# CUK_3Ph_sig_conditioner.net
KiCad netlist of a schematic drawn in Altium Designer
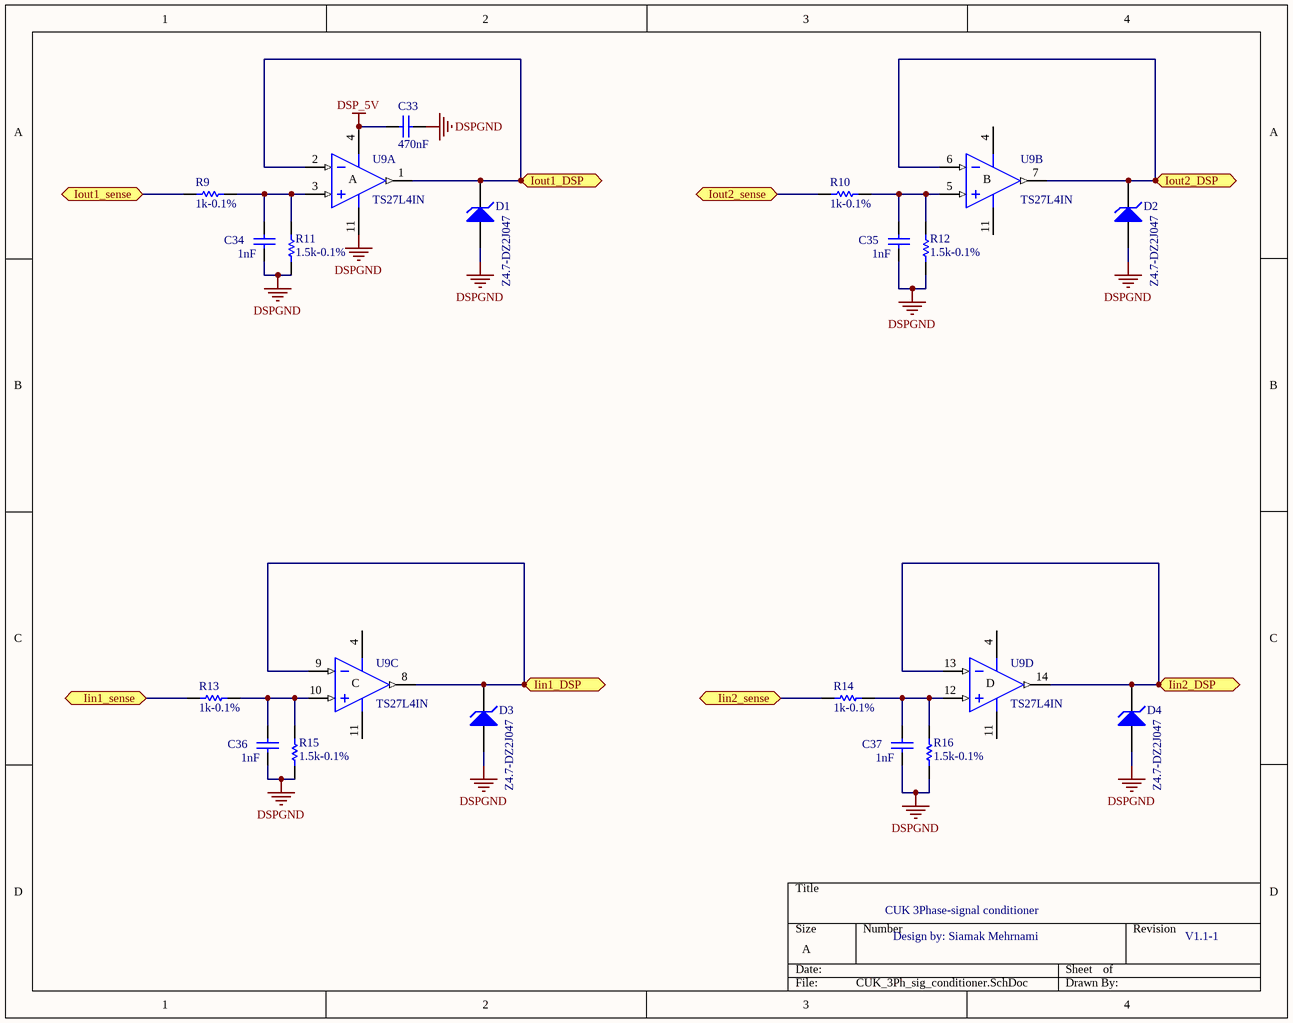
[diagram p0: CUK_3Ph_sig_conditioner.SchDoc]

(export (version "E")
  (design (tool "Eeschema 10.0.6"))
  (components
    (comp (ref "C33")
      (value "470nF")
      (footprint "Capacitor 0805")
      (description "Capacitor")
      (fields (field (name "Comment") "Cap") (field (name "PUBLISHER") "Altium Limited"))
      (libsource (lib "Miscellaneous Devices") (part "Cap"))
    )
    (comp (ref "C34")
      (value "1nF")
      (footprint "Capacitor 0805")
      (description "Capacitor")
      (fields (field (name "Comment") "Cap") (field (name "PUBLISHER") "Altium Limited"))
      (libsource (lib "Miscellaneous Devices") (part "Cap"))
    )
    (comp (ref "C35")
      (value "1nF")
      (footprint "Capacitor 0805")
      (description "Capacitor")
      (fields (field (name "Comment") "Cap") (field (name "PUBLISHER") "Altium Limited"))
      (libsource (lib "Miscellaneous Devices") (part "Cap"))
    )
    (comp (ref "C36")
      (value "1nF")
      (footprint "Capacitor 0805")
      (description "Capacitor")
      (fields (field (name "Comment") "Cap") (field (name "PUBLISHER") "Altium Limited"))
      (libsource (lib "Miscellaneous Devices") (part "Cap"))
    )
    (comp (ref "C37")
      (value "1nF")
      (footprint "Capacitor 0805")
      (description "Capacitor")
      (fields (field (name "Comment") "Cap") (field (name "PUBLISHER") "Altium Limited"))
      (libsource (lib "Miscellaneous Devices") (part "Cap"))
    )
    (comp (ref "D1")
      (value "Z4.7-DZ2J047")
      (footprint "Zener DZ2J047")
      (description "Zener Diode")
      (fields (field (name "PUBLISHER") "Altium Limited"))
      (libsource (lib "Miscellaneous Devices") (part "D Zener"))
    )
    (comp (ref "D2")
      (value "Z4.7-DZ2J047")
      (footprint "Zener DZ2J047")
      (description "Zener Diode")
      (fields (field (name "PUBLISHER") "Altium Limited"))
      (libsource (lib "Miscellaneous Devices") (part "D Zener"))
    )
    (comp (ref "D3")
      (value "Z4.7-DZ2J047")
      (footprint "Zener DZ2J047")
      (description "Zener Diode")
      (fields (field (name "PUBLISHER") "Altium Limited"))
      (libsource (lib "Miscellaneous Devices") (part "D Zener"))
    )
    (comp (ref "D4")
      (value "Z4.7-DZ2J047")
      (footprint "Zener DZ2J047")
      (description "Zener Diode")
      (fields (field (name "PUBLISHER") "Altium Limited"))
      (libsource (lib "Miscellaneous Devices") (part "D Zener"))
    )
    (comp (ref "R9")
      (value "1k-0.1%")
      (footprint "0805 RES")
      (description "Resistor")
      (fields (field (name "Comment") "Res1") (field (name "PUBLISHER") "Altium Limited"))
      (libsource (lib "Miscellaneous Devices") (part "Res1"))
    )
    (comp (ref "R10")
      (value "1k-0.1%")
      (footprint "0805 RES")
      (description "Resistor")
      (fields (field (name "Comment") "Res1") (field (name "PUBLISHER") "Altium Limited"))
      (libsource (lib "Miscellaneous Devices") (part "Res1"))
    )
    (comp (ref "R11")
      (value "1.5k-0.1%")
      (footprint "0805 RES")
      (description "Resistor")
      (fields (field (name "Comment") "Res1") (field (name "PUBLISHER") "Altium Limited"))
      (libsource (lib "Miscellaneous Devices") (part "Res1"))
    )
    (comp (ref "R12")
      (value "1.5k-0.1%")
      (footprint "0805 RES")
      (description "Resistor")
      (fields (field (name "Comment") "Res1") (field (name "PUBLISHER") "Altium Limited"))
      (libsource (lib "Miscellaneous Devices") (part "Res1"))
    )
    (comp (ref "R13")
      (value "1k-0.1%")
      (footprint "0805 RES")
      (description "Resistor")
      (fields (field (name "Comment") "Res1") (field (name "PUBLISHER") "Altium Limited"))
      (libsource (lib "Miscellaneous Devices") (part "Res1"))
    )
    (comp (ref "R14")
      (value "1k-0.1%")
      (footprint "0805 RES")
      (description "Resistor")
      (fields (field (name "Comment") "Res1") (field (name "PUBLISHER") "Altium Limited"))
      (libsource (lib "Miscellaneous Devices") (part "Res1"))
    )
    (comp (ref "R15")
      (value "1.5k-0.1%")
      (footprint "0805 RES")
      (description "Resistor")
      (fields (field (name "Comment") "Res1") (field (name "PUBLISHER") "Altium Limited"))
      (libsource (lib "Miscellaneous Devices") (part "Res1"))
    )
    (comp (ref "R16")
      (value "1.5k-0.1%")
      (footprint "0805 RES")
      (description "Resistor")
      (fields (field (name "Comment") "Res1") (field (name "PUBLISHER") "Altium Limited"))
      (libsource (lib "Miscellaneous Devices") (part "Res1"))
    )
    (comp (ref "U9")
      (value "TS27L4IN")
      (footprint "DIP14")
      (description "Very Low-Power CMOS Quad Operational Amplifier")
      (fields (field (name "PUBLISHER") "Altium Limited"))
      (libsource (lib "ST Operational Amplifier") (part "TS27L4AMD"))
    )
  )
  (nets
    (net (code "1") (name "/Iin1_DSP") (class "Default")
      (node (ref "D3") (pin "2") (pinfunction "K_2") (pintype "passive"))
      (node (ref "U9") (pin "8") (pinfunction "OUT_8") (pintype "output"))
      (node (ref "U9") (pin "9") (pinfunction "IN-_9") (pintype "input"))
    )
    (net (code "2") (name "/Iin1_sense") (class "Default")
      (node (ref "R13") (pin "2") (pinfunction "2_2") (pintype "passive"))
    )
    (net (code "3") (name "/Iin2_DSP") (class "Default")
      (node (ref "D4") (pin "2") (pinfunction "K_2") (pintype "passive"))
      (node (ref "U9") (pin "13") (pinfunction "IN-_13") (pintype "input"))
      (node (ref "U9") (pin "14") (pinfunction "OUT_14") (pintype "output"))
    )
    (net (code "4") (name "/Iin2_sense") (class "Default")
      (node (ref "R14") (pin "2") (pinfunction "2_2") (pintype "passive"))
    )
    (net (code "5") (name "/Iout1_DSP") (class "Default")
      (node (ref "D1") (pin "2") (pinfunction "K_2") (pintype "passive"))
      (node (ref "U9") (pin "1") (pinfunction "OUT_1") (pintype "output"))
      (node (ref "U9") (pin "2") (pinfunction "IN-_2") (pintype "input"))
    )
    (net (code "6") (name "/Iout1_sense") (class "Default")
      (node (ref "R9") (pin "2") (pinfunction "2_2") (pintype "passive"))
    )
    (net (code "7") (name "/Iout2_DSP") (class "Default")
      (node (ref "D2") (pin "2") (pinfunction "K_2") (pintype "passive"))
      (node (ref "U9") (pin "6") (pinfunction "IN-_6") (pintype "input"))
      (node (ref "U9") (pin "7") (pinfunction "OUT_7") (pintype "output"))
    )
    (net (code "8") (name "/Iout2_sense") (class "Default")
      (node (ref "R10") (pin "2") (pinfunction "2_2") (pintype "passive"))
    )
    (net (code "9") (name "DSPGND") (class "Default")
      (node (ref "C33") (pin "1") (pinfunction "1_1") (pintype "passive"))
      (node (ref "C34") (pin "1") (pinfunction "1_1") (pintype "passive"))
      (node (ref "C35") (pin "1") (pinfunction "1_1") (pintype "passive"))
      (node (ref "C36") (pin "1") (pinfunction "1_1") (pintype "passive"))
      (node (ref "C37") (pin "1") (pinfunction "1_1") (pintype "passive"))
      (node (ref "D1") (pin "1") (pinfunction "A_1") (pintype "passive"))
      (node (ref "D2") (pin "1") (pinfunction "A_1") (pintype "passive"))
      (node (ref "D3") (pin "1") (pinfunction "A_1") (pintype "passive"))
      (node (ref "D4") (pin "1") (pinfunction "A_1") (pintype "passive"))
      (node (ref "R11") (pin "1") (pinfunction "1_1") (pintype "passive"))
      (node (ref "R12") (pin "1") (pinfunction "1_1") (pintype "passive"))
      (node (ref "R15") (pin "1") (pinfunction "1_1") (pintype "passive"))
      (node (ref "R16") (pin "1") (pinfunction "1_1") (pintype "passive"))
      (node (ref "U9") (pin "11") (pinfunction "V-_11") (pintype "power_in"))
    )
    (net (code "10") (name "DSP_5V") (class "Default")
      (node (ref "C33") (pin "2") (pinfunction "2_2") (pintype "passive"))
      (node (ref "U9") (pin "4") (pinfunction "V+_4") (pintype "power_in"))
    )
    (net (code "11") (name "Net-(U9A-IN+)") (class "Default")
      (node (ref "C34") (pin "2") (pinfunction "2_2") (pintype "passive"))
      (node (ref "R11") (pin "2") (pinfunction "2_2") (pintype "passive"))
      (node (ref "R9") (pin "1") (pinfunction "1_1") (pintype "passive"))
      (node (ref "U9") (pin "3") (pinfunction "IN+_3") (pintype "input"))
    )
    (net (code "12") (name "Net-(U9B-IN+)") (class "Default")
      (node (ref "C35") (pin "2") (pinfunction "2_2") (pintype "passive"))
      (node (ref "R10") (pin "1") (pinfunction "1_1") (pintype "passive"))
      (node (ref "R12") (pin "2") (pinfunction "2_2") (pintype "passive"))
      (node (ref "U9") (pin "5") (pinfunction "IN+_5") (pintype "input"))
    )
    (net (code "13") (name "Net-(U9C-IN+)") (class "Default")
      (node (ref "C36") (pin "2") (pinfunction "2_2") (pintype "passive"))
      (node (ref "R13") (pin "1") (pinfunction "1_1") (pintype "passive"))
      (node (ref "R15") (pin "2") (pinfunction "2_2") (pintype "passive"))
      (node (ref "U9") (pin "10") (pinfunction "IN+_10") (pintype "input"))
    )
    (net (code "14") (name "Net-(U9D-IN+)") (class "Default")
      (node (ref "C37") (pin "2") (pinfunction "2_2") (pintype "passive"))
      (node (ref "R14") (pin "1") (pinfunction "1_1") (pintype "passive"))
      (node (ref "R16") (pin "2") (pinfunction "2_2") (pintype "passive"))
      (node (ref "U9") (pin "12") (pinfunction "IN+_12") (pintype "input"))
    )
    (net (code "15") (name "unconnected-(U9B-V+-Pad4)") (class "Default")
      (node (ref "U9") (pin "4") (pinfunction "V+_4") (pintype "power_in"))
    )
    (net (code "16") (name "unconnected-(U9B-V--Pad11)") (class "Default")
      (node (ref "U9") (pin "11") (pinfunction "V-_11") (pintype "power_in"))
    )
    (net (code "17") (name "unconnected-(U9C-V+-Pad4)") (class "Default")
      (node (ref "U9") (pin "4") (pinfunction "V+_4") (pintype "power_in"))
    )
    (net (code "18") (name "unconnected-(U9C-V--Pad11)") (class "Default")
      (node (ref "U9") (pin "11") (pinfunction "V-_11") (pintype "power_in"))
    )
    (net (code "19") (name "unconnected-(U9D-V+-Pad4)") (class "Default")
      (node (ref "U9") (pin "4") (pinfunction "V+_4") (pintype "power_in"))
    )
    (net (code "20") (name "unconnected-(U9D-V--Pad11)") (class "Default")
      (node (ref "U9") (pin "11") (pinfunction "V-_11") (pintype "power_in"))
    )
  )
)
